# 5DPD8_v1_0_OS_Sheet4.net
KiCad netlist of a schematic drawn in Altium Designer
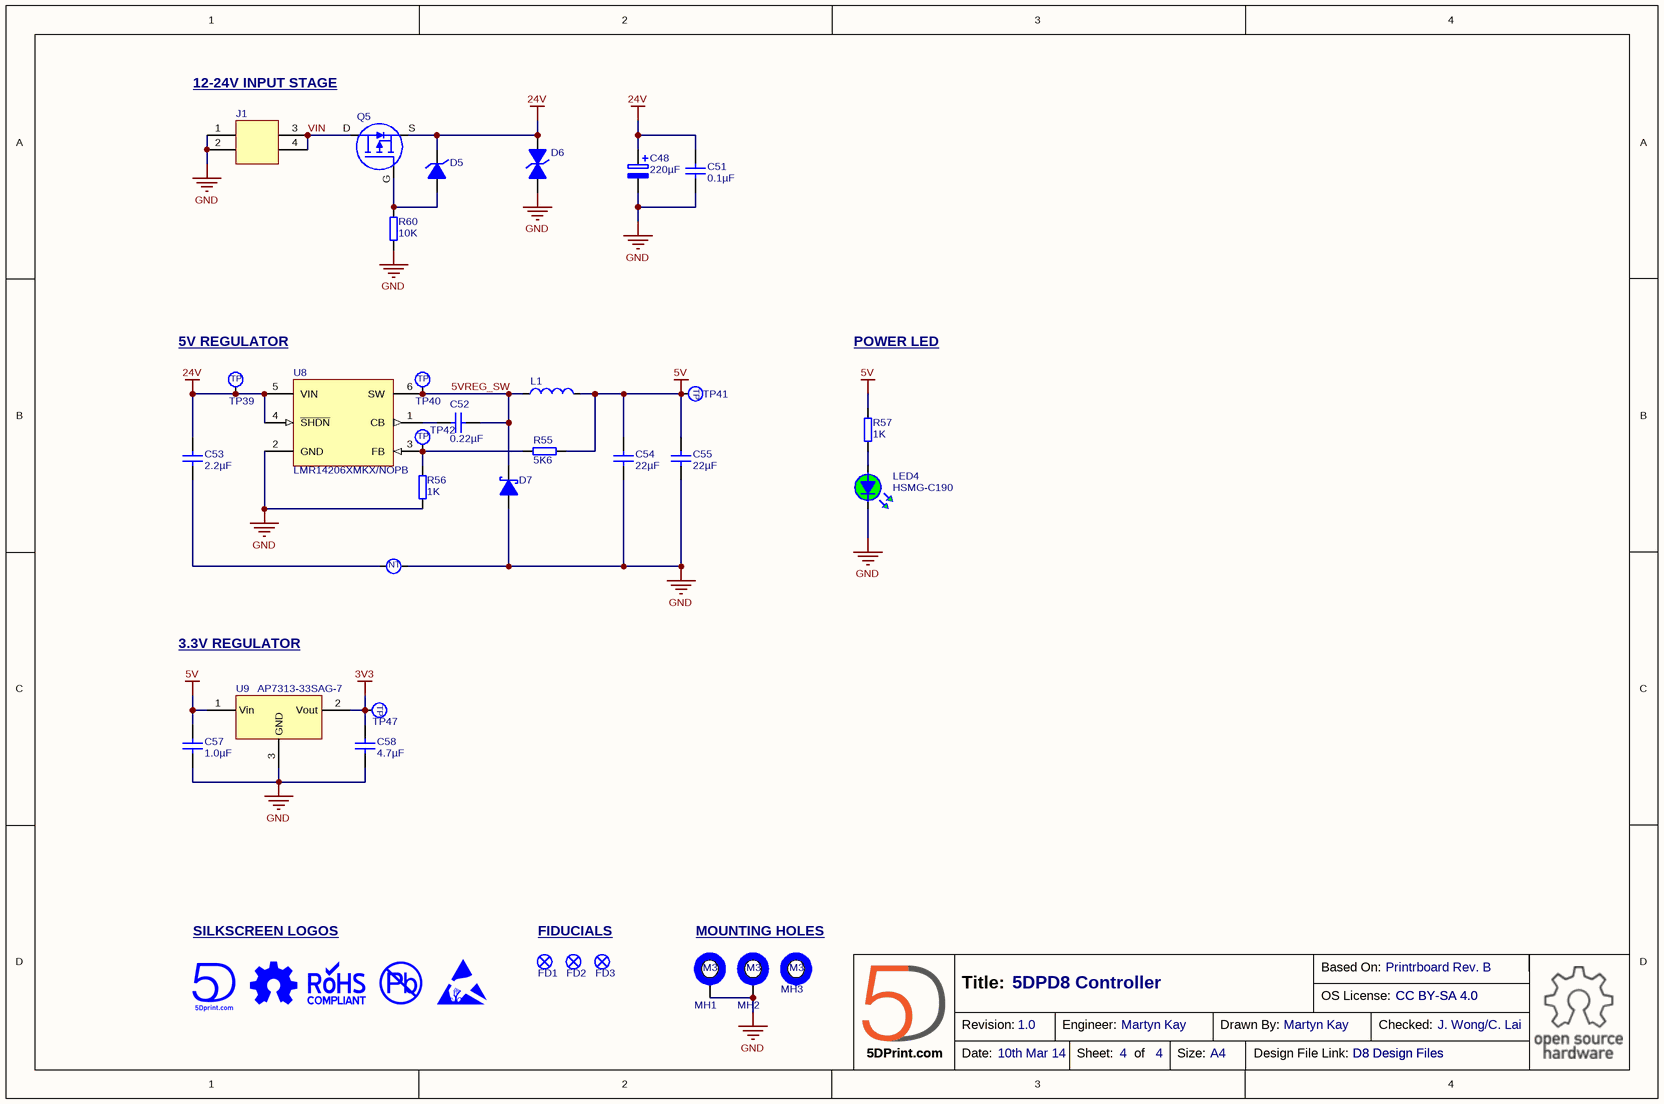
[diagram p0: 5DPD8_v1.0_OS_Sheet4.SchDoc]

(export (version "E")
  (design (tool "Eeschema 10.0.6"))
  (components
    (comp (ref "C48")
      (value "220µF")
      (footprint "CAPRAD8X11.5")
      (description "CAP ALUM 220UF 35V 20% RADIAL")
      (fields
        (field (name "MANUFACTURER") "Rubycon")
        (field (name "MANUFACTURERPARTNUMBER") "35ZLH220MEFC8X11.5")
      )
      (libsource (lib "5DPD8") (part "CAP_RAD-ALU-220UF-35V-20%"))
    )
    (comp (ref "C51")
      (value "0.1µF")
      (footprint "CAPC0603(1608)100_N")
      (description "CAP CER 0.1UF 50V 10% X7R 0603")
      (fields
        (field (name "MANUFACTURER") "Yageo")
        (field (name "MANUFACTURERPARTNUMBER") "CC0603KRX7R9BB104")
      )
      (libsource (lib "5DPD8") (part "C0603-0.1UF-50V-10%-X7R"))
    )
    (comp (ref "C52")
      (value "0.22µF")
      (footprint "CAPC0603(1608)100_N")
      (description "CAP CER 0.22UF 50V 10% X7R 0603")
      (fields
        (field (name "MANUFACTURER") "TDK Corporation")
        (field (name "MANUFACTURERPARTNUMBER") "C1608X7R1H224K080AB")
      )
      (libsource (lib "5DPD8") (part "C0603-0.22UF-50V-10%-X7R"))
    )
    (comp (ref "C53")
      (value "2.2µF")
      (footprint "CAPC0805(2012)145_N")
      (description "CAP CER 2.2UF 50V 10% X7R 0805")
      (fields
        (field (name "MANUFACTURER") "Taiyo Yuden")
        (field (name "MANUFACTURERPARTNUMBER") "UMK212BB7225KG-T")
      )
      (libsource (lib "5DPD8") (part "C0805-2.2UF-50V-10%-X7R"))
    )
    (comp (ref "C54")
      (value "22µF")
      (footprint "CAPC0805(2012)145_N")
      (description "CAP CER 22UF 10V 10% X5R 0805")
      (fields
        (field (name "MANUFACTURER") "TDK Corporation")
        (field (name "MANUFACTURERPARTNUMBER") "C2012X5R1A226K125AB")
      )
      (libsource (lib "5DPD8") (part "C0805-22UF-10V-10%-X5R"))
    )
    (comp (ref "C55")
      (value "22µF")
      (footprint "CAPC0805(2012)145_N")
      (description "CAP CER 22UF 10V 10% X5R 0805")
      (fields
        (field (name "MANUFACTURER") "TDK Corporation")
        (field (name "MANUFACTURERPARTNUMBER") "C2012X5R1A226K125AB")
      )
      (libsource (lib "5DPD8") (part "C0805-22UF-10V-10%-X5R"))
    )
    (comp (ref "C57")
      (value "1.0µF")
      (footprint "CAPC0603(1608)100_N")
      (description "CAP CER 1UF 10V 10% X7R 0603")
      (fields
        (field (name "MANUFACTURER") "Taiyo Yuden")
        (field (name "MANUFACTURERPARTNUMBER") "LMK107B7105KA-T")
      )
      (libsource (lib "5DPD8") (part "C0603-1UF-10V-10%-X7R"))
    )
    (comp (ref "C58")
      (value "4.7µF")
      (footprint "CAPC0603(1608)100_N")
      (description "CAP CER 4.7UF 6.3V 10% X5R 0603")
      (fields
        (field (name "MANUFACTURER") "Taiyo Yuden")
        (field (name "MANUFACTURERPARTNUMBER") "JMK107BJ475KA-T")
      )
      (libsource (lib "5DPD8") (part "C0603-4.7UF-6.3V-10%-X5R"))
    )
    (comp (ref "D5")
      (value "BZV55-C10,115")
      (footprint "DIOMELF3515N")
      (description "DIODE ZENER 10V 500MW LLDS")
      (fields (field (name "MANUFACTURER") "NXP Semiconductors") (field (name "TOLERANCE") "±5%"))
      (libsource (lib "5DPD8") (part "DIO_BZV55-C10,115"))
    )
    (comp (ref "D6")
      (value "SMAJ24CA")
      (footprint "DIOM4326X23N-BI")
      (description "DIODE TVS 24V 400W BIDIR 5% SMA")
      (fields (field (name "MANUFACTURER") "Littelfuse Inc"))
      (libsource (lib "5DPD8") (part "DIO_SMAJ24CA"))
    )
    (comp (ref "D7")
      (value "B140-13-F")
      (footprint "DIOM4326X23N-UNI")
      (description "DIODE SCHOTTKY 40V 1A SMA")
      (fields (field (name "MANUFACTURER") "Diodes Inc"))
      (libsource (lib "5DPD8") (part "DIO_B140-13-F"))
    )
    (comp (ref "FD1")
      (value "MECH_FIDUCIAL")
      (footprint "FIDUCIAL-1MM")
      (description "Fiducial Marker")
      (libsource (lib "5DPD8") (part "MECH_FIDUCIAL"))
    )
    (comp (ref "FD2")
      (value "MECH_FIDUCIAL")
      (footprint "FIDUCIAL-1MM")
      (description "Fiducial Marker")
      (libsource (lib "5DPD8") (part "MECH_FIDUCIAL"))
    )
    (comp (ref "FD3")
      (value "MECH_FIDUCIAL")
      (footprint "FIDUCIAL-1MM")
      (description "Fiducial Marker")
      (libsource (lib "5DPD8") (part "MECH_FIDUCIAL"))
    )
    (comp (ref "J1")
      (value "0039281043")
      (footprint "MOLEX_39-28-1043")
      (description "CONN HEADER 4POS 4.2MM VERT TIN")
      (fields (field (name "MANUFACTURER") "Molex Inc"))
      (libsource (lib "5DPD8") (part "CON_MLX_39-28-1043"))
    )
    (comp (ref "L1")
      (value "SRN6045-220M")
      (footprint "INDP6060X45N")
      (description "INDUCTOR POWER SHIELD 22UH SMD")
      (fields (field (name "MANUFACTURER") "Bourns Inc.") (field (name "TOLERANCE") "±20%"))
      (libsource (lib "5DPD8") (part "MAG_SRN6045-220M"))
    )
    (comp (ref "LED4")
      (value "HSMG-C190")
      (footprint "LEDC0603(1608)_N-GRN")
      (description "LED 570NM GREEN DIFF 0603 SMD")
      (fields (field (name "MANUFACTURER") "Avago Technologies US Inc."))
      (libsource (lib "5DPD8") (part "LED_HSMG-C190"))
    )
    (comp (ref "LG1")
      (value "5DPRINT")
      (footprint "5DPRINT-10MM")
      (description "5D PRINT SILKSCREEN LOGO")
      (libsource (lib "Logos") (part "5DPRINT"))
    )
    (comp (ref "LG2")
      (value "ESD")
      (footprint "ESD-5MM")
      (description "ESD WARNING SILKSCREEN LOGO")
      (libsource (lib "Logos") (part "ESD"))
    )
    (comp (ref "LG3")
      (value "LEADFREE")
      (footprint "LEADFREE-5MM")
      (description "Pb-FREE SILKSCREEN LOGO")
      (libsource (lib "Logos") (part "LEADFREE"))
    )
    (comp (ref "LG4")
      (value "OSHW_COG")
      (footprint "OSHW_COG-5MM")
      (description "OSHW COG SILKSCREEN LOGO")
      (libsource (lib "Logos") (part "OSHW_COG"))
    )
    (comp (ref "LG6")
      (value "RoHS")
      (footprint "RoHS-5MM")
      (description "RoHS SILKSCREEN LOGO")
      (libsource (lib "Logos") (part "RoHS"))
    )
    (comp (ref "MH1")
      (value "MECH_MH-M3")
      (footprint "M3 MOUNT-3.4MM")
      (description "M3 Mounting Hole")
      (libsource (lib "5DPD8") (part "MECH_MH-M3"))
    )
    (comp (ref "MH2")
      (value "MECH_MH-M3")
      (footprint "M3 MOUNT-3.4MM")
      (description "M3 Mounting Hole")
      (libsource (lib "5DPD8") (part "MECH_MH-M3"))
    )
    (comp (ref "MH3")
      (value "MECH_MH-M3-NP")
      (footprint "M3 MOUNT-3.4MM-NOPAD")
      (description "M3 Mounting Hole - no pad, unplated")
      (libsource (lib "5DPD8") (part "MECH_MH-M3-NP"))
    )
    (comp (ref "NT1")
      (value "NET_TIE")
      (footprint "NET_TIE-2NET_12MM")
      (description "NET TIE")
      (libsource (lib "5DPD8") (part "NET_TIE"))
    )
    (comp (ref "Q5")
      (value "SIS427EDN-T1-GE3")
      (footprint "POWERPAK1212-8S")
      (description "MOSFET P-CHAN 30V 1212-8")
      (fields (field (name "MANUFACTURER") "Vishay Siliconix"))
      (libsource (lib "5DPD8") (part "FETP_SIS427EDN-T1-GE3"))
    )
    (comp (ref "R55")
      (value "5K6")
      (footprint "RESC0603(1608)_N")
      (description "RES 5.60K OHM 1/10W 1% 0603 SMD")
      (fields (field (name "MANUFACTURER") "Yageo") (field (name "MANUFACTURERPARTNUMBER") "RC0603FR-075K6L"))
      (libsource (lib "5DPD8") (part "R0603-5K6-0.1W-1%"))
    )
    (comp (ref "R56")
      (value "1K")
      (footprint "RESC0603(1608)_N")
      (description "RES 1.00K OHM 1/10W 1% 0603 SMD")
      (fields (field (name "MANUFACTURER") "Yageo") (field (name "MANUFACTURERPARTNUMBER") "RC0603FR-071KL"))
      (libsource (lib "5DPD8") (part "R0603-1K-0.1W-1%"))
    )
    (comp (ref "R57")
      (value "1K")
      (footprint "RESC0603(1608)_N")
      (description "RES 1.00K OHM 1/10W 1% 0603 SMD")
      (fields (field (name "MANUFACTURER") "Yageo") (field (name "MANUFACTURERPARTNUMBER") "RC0603FR-071KL"))
      (libsource (lib "5DPD8") (part "R0603-1K-0.1W-1%"))
    )
    (comp (ref "R60")
      (value "10K")
      (footprint "RESC0603(1608)_N")
      (description "RES 10K OHM 1/10W 5% 0603 SMD")
      (fields (field (name "MANUFACTURER") "Yageo") (field (name "MANUFACTURERPARTNUMBER") "RC0603JR-0710KL"))
      (libsource (lib "5DPD8") (part "R0603-10K-0.1W-5%"))
    )
    (comp (ref "TP39")
      (value "TESTPOINT")
      (footprint "TESTPOINT")
      (libsource (lib "5DPD8") (part "TESTPOINT"))
    )
    (comp (ref "TP40")
      (value "TESTPOINT")
      (footprint "TESTPOINT")
      (libsource (lib "5DPD8") (part "TESTPOINT"))
    )
    (comp (ref "TP41")
      (value "TESTPOINT")
      (footprint "TESTPOINT")
      (libsource (lib "5DPD8") (part "TESTPOINT"))
    )
    (comp (ref "TP42")
      (value "TESTPOINT")
      (footprint "TESTPOINT")
      (libsource (lib "5DPD8") (part "TESTPOINT"))
    )
    (comp (ref "TP47")
      (value "TESTPOINT")
      (footprint "TESTPOINT")
      (libsource (lib "5DPD8") (part "TESTPOINT"))
    )
    (comp (ref "U8")
      (value "LMR14206XMKX/NOPB")
      (footprint "MK06A_N")
      (description "IC REG BUCK ADJ 0.6A 6TSOT")
      (fields (field (name "MANUFACTURER") "Texas Instruments"))
      (libsource (lib "5DPD8") (part "IC_LMR14206XMKX/NOPB"))
    )
    (comp (ref "U9")
      (value "AP7313-33SAG-7")
      (footprint "SOT95P237X112-3N")
      (description "IC REG LDO 3.3V 0.15A SOT23-3")
      (fields (field (name "MANUFACTURER") "Diodes Inc"))
      (libsource (lib "5DPD8") (part "IC_AP7313-33SAG-7"))
    )
  )
  (nets
    (net (code "1") (name "/5VREG_SW") (class "Default")
      (node (ref "C52") (pin "2") (pinfunction "2_2") (pintype "passive"))
      (node (ref "D7") (pin "K") (pinfunction "K_K") (pintype "passive"))
      (node (ref "L1") (pin "1") (pinfunction "1_1") (pintype "passive"))
      (node (ref "TP40") (pin "1") (pinfunction "1_1") (pintype "passive"))
      (node (ref "U8") (pin "6") (pinfunction "SW_6") (pintype "power_in"))
    )
    (net (code "2") (name "/VIN") (class "Default")
      (node (ref "J1") (pin "3") (pinfunction "3_3") (pintype "passive"))
      (node (ref "J1") (pin "4") (pinfunction "4_4") (pintype "passive"))
      (node (ref "Q5") (pin "D") (pinfunction "D_D") (pintype "passive"))
    )
    (net (code "3") (name "3V3") (class "Default")
      (node (ref "C58") (pin "2") (pinfunction "2_2") (pintype "passive"))
      (node (ref "TP47") (pin "1") (pinfunction "1_1") (pintype "passive"))
      (node (ref "U9") (pin "2") (pinfunction "Vout_2") (pintype "power_in"))
    )
    (net (code "4") (name "5V") (class "Default")
      (node (ref "C54") (pin "2") (pinfunction "2_2") (pintype "passive"))
      (node (ref "C55") (pin "2") (pinfunction "2_2") (pintype "passive"))
      (node (ref "C57") (pin "2") (pinfunction "2_2") (pintype "passive"))
      (node (ref "L1") (pin "2") (pinfunction "2_2") (pintype "passive"))
      (node (ref "R55") (pin "2") (pinfunction "2_2") (pintype "passive"))
      (node (ref "R57") (pin "2") (pinfunction "2_2") (pintype "passive"))
      (node (ref "TP41") (pin "1") (pinfunction "1_1") (pintype "passive"))
      (node (ref "U9") (pin "1") (pinfunction "Vin_1") (pintype "power_in"))
    )
    (net (code "5") (name "24V") (class "Default")
      (node (ref "C48") (pin "1") (pinfunction "+_1") (pintype "passive"))
      (node (ref "C51") (pin "2") (pinfunction "2_2") (pintype "passive"))
      (node (ref "C53") (pin "2") (pinfunction "2_2") (pintype "passive"))
      (node (ref "D5") (pin "K") (pinfunction "K_K") (pintype "passive"))
      (node (ref "D6") (pin "1") (pinfunction "1_1") (pintype "passive"))
      (node (ref "Q5") (pin "S") (pinfunction "S_S") (pintype "passive"))
      (node (ref "TP39") (pin "1") (pinfunction "1_1") (pintype "passive"))
      (node (ref "U8") (pin "4") (pinfunction "~{SHDN}_4") (pintype "input"))
      (node (ref "U8") (pin "5") (pinfunction "VIN_5") (pintype "power_in"))
    )
    (net (code "6") (name "GND") (class "Default")
      (node (ref "C48") (pin "2") (pinfunction "-_2") (pintype "passive"))
      (node (ref "C51") (pin "1") (pinfunction "1_1") (pintype "passive"))
      (node (ref "C54") (pin "1") (pinfunction "1_1") (pintype "passive"))
      (node (ref "C55") (pin "1") (pinfunction "1_1") (pintype "passive"))
      (node (ref "C57") (pin "1") (pinfunction "1_1") (pintype "passive"))
      (node (ref "C58") (pin "1") (pinfunction "1_1") (pintype "passive"))
      (node (ref "D6") (pin "2") (pinfunction "2_2") (pintype "passive"))
      (node (ref "D7") (pin "A") (pinfunction "A_A") (pintype "passive"))
      (node (ref "J1") (pin "1") (pinfunction "1_1") (pintype "passive"))
      (node (ref "J1") (pin "2") (pinfunction "2_2") (pintype "passive"))
      (node (ref "LED4") (pin "K") (pinfunction "K_K") (pintype "passive"))
      (node (ref "MH1") (pin "MH") (pinfunction "1_MH") (pintype "passive"))
      (node (ref "MH2") (pin "MH") (pinfunction "1_MH") (pintype "passive"))
      (node (ref "NT1") (pin "2") (pinfunction "2_2") (pintype "passive"))
      (node (ref "R56") (pin "1") (pinfunction "1_1") (pintype "passive"))
      (node (ref "R60") (pin "1") (pinfunction "1_1") (pintype "passive"))
      (node (ref "U8") (pin "2") (pinfunction "GND_2") (pintype "power_in"))
      (node (ref "U9") (pin "3") (pinfunction "GND_3") (pintype "power_in"))
    )
    (net (code "7") (name "Net-(C53-Pad1)") (class "Default")
      (node (ref "C53") (pin "1") (pinfunction "1_1") (pintype "passive"))
      (node (ref "NT1") (pin "1") (pinfunction "1_1") (pintype "passive"))
    )
    (net (code "8") (name "Net-(D5-PadA)") (class "Default")
      (node (ref "D5") (pin "A") (pinfunction "A_A") (pintype "passive"))
      (node (ref "Q5") (pin "G") (pinfunction "G_G") (pintype "passive"))
      (node (ref "R60") (pin "2") (pinfunction "2_2") (pintype "passive"))
    )
    (net (code "9") (name "Net-(LED4-PadA)") (class "Default")
      (node (ref "LED4") (pin "A") (pinfunction "A_A") (pintype "passive"))
      (node (ref "R57") (pin "1") (pinfunction "1_1") (pintype "passive"))
    )
    (net (code "10") (name "Net-(U8-CB)") (class "Default")
      (node (ref "C52") (pin "1") (pinfunction "1_1") (pintype "passive"))
      (node (ref "U8") (pin "1") (pinfunction "CB_1") (pintype "output"))
    )
    (net (code "11") (name "Net-(U8-FB)") (class "Default")
      (node (ref "R55") (pin "1") (pinfunction "1_1") (pintype "passive"))
      (node (ref "R56") (pin "2") (pinfunction "2_2") (pintype "passive"))
      (node (ref "TP42") (pin "1") (pinfunction "1_1") (pintype "passive"))
      (node (ref "U8") (pin "3") (pinfunction "FB_3") (pintype "input"))
    )
  )
)
